# S1-C1-UPS.net
KiCad netlist of a schematic drawn in Altium Designer
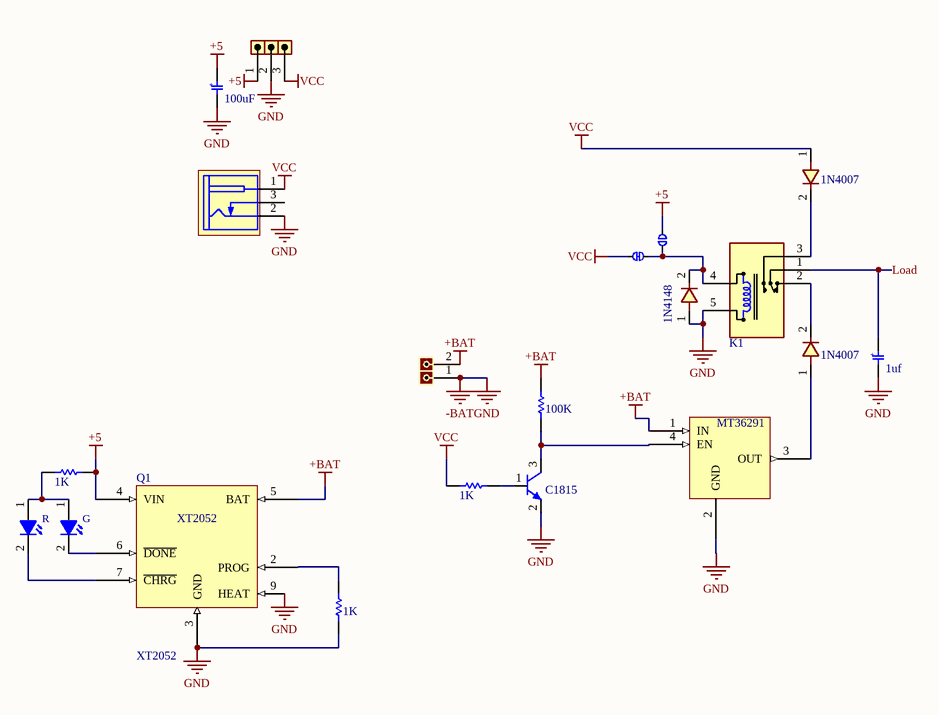
[diagram p0: S1-C1-UPS.SchDoc]

(export (version "E")
  (design (tool "Eeschema 10.0.6"))
  (components
    (comp (ref "*1") (value "SB-NC") (footprint "SB-NC") (libsource (lib "CustomLIB") (part "SB-NC")))
    (comp (ref "*2")
      (value "MT36291 Module")
      (footprint "Module")
      (libsource (lib "CustomLIB") (part "MT36291 Module"))
    )
    (comp (ref "C1")
      (value "100uF")
      (footprint "C_EL_8X12")
      (description "Capacitor Electrical THD")
      (libsource (lib "Capacitor") (part "Capacitor Electrical THD"))
    )
    (comp (ref "C2")
      (value "1uf")
      (footprint "C_EL_10X12")
      (description "Capacitor Electrical THD")
      (libsource (lib "Capacitor") (part "Capacitor Electrical THD"))
    )
    (comp (ref "D1")
      (value "1N4007")
      (footprint "D_SMA")
      (description "DIODE, GENERAL PURPOSE, 1000V/1A")
      (fields (field (name "Comment") "1N4007 SMD M7"))
      (libsource (lib "Diode") (part "1N4007 SMD M7"))
    )
    (comp (ref "D2")
      (value "1N4148")
      (footprint "D_SMA")
      (description "DIODE, GENERAL PURPOSE, 1000V/1A")
      (fields (field (name "Comment") "1N4007 SMD M7"))
      (libsource (lib "Diode") (part "1N4007 SMD M7"))
    )
    (comp (ref "D3")
      (value "1N4007")
      (footprint "D_SMA")
      (description "DIODE, GENERAL PURPOSE, 1000V/1A")
      (fields (field (name "Comment") "1N4007 SMD M7"))
      (libsource (lib "Diode") (part "1N4007 SMD M7"))
    )
    (comp (ref "D4")
      (value "R")
      (footprint "LED SMD 0805 (Red)")
      (description "LED SMD 0805")
      (libsource (lib "LED") (part "LED SMD 0805"))
    )
    (comp (ref "D5")
      (value "G")
      (footprint "LED SMD 0805 (Green)")
      (description "LED SMD 0805")
      (libsource (lib "LED") (part "LED SMD 0805"))
    )
    (comp (ref "J1")
      (value "Female Header Single 3")
      (footprint "HDR_F_1X3")
      (description "Female, pitch: 2.54mm")
      (libsource (lib "Header") (part "Female Header Single 3"))
    )
    (comp (ref "J2")
      (value "Power Jack")
      (footprint "POWER J1")
      (libsource (lib "Socket") (part "Power Jack"))
    )
    (comp (ref "K1")
      (value "RELAY SPST 5 Pin Millon")
      (footprint "REL_SPDT_5_2216")
      (description "Relay")
      (libsource (lib "Relay") (part "RELAY SPST 5 Pin Millon"))
    )
    (comp (ref "P1")
      (value "Male Header Single 02")
      (footprint "MHDR1X02-254P")
      (description "Male, pitch: 2.54mm")
      (libsource (lib "Header") (part "Male Header Single 02"))
    )
    (comp (ref "Q1") (value "XT2052") (footprint "XT2052") (libsource (lib "XT2052") (part "XT2052")))
    (comp (ref "Q2")
      (value "C1815")
      (footprint "SOT-23")
      (fields (field (name "Comment") "C1815 NPN"))
      (libsource (lib "Transistor") (part "C1815 NPN"))
    )
    (comp (ref "R1")
      (value "100K")
      (footprint "R0805")
      (description "Resistor SMD 0805")
      (libsource (lib "Resistor") (part "Resistor SMD 0805"))
    )
    (comp (ref "R2")
      (value "1K")
      (footprint "R0805")
      (description "Resistor SMD 0805")
      (libsource (lib "Resistor") (part "Resistor SMD 0805"))
    )
    (comp (ref "R3")
      (value "1K")
      (footprint "R0805")
      (description "Resistor SMD 0805")
      (libsource (lib "Resistor") (part "Resistor SMD 0805"))
    )
    (comp (ref "R4")
      (value "1K")
      (footprint "R0805")
      (description "Resistor SMD 0805")
      (libsource (lib "Resistor") (part "Resistor SMD 0805"))
    )
    (comp (ref "SB1") (value "Solid Bridge") (footprint "SB-NO") (libsource (lib "CustomLIB") (part "SB-NO")))
  )
  (nets
    (net (code "1") (name "+5") (class "Default")
      (node (ref "C1") (pin "1") (pinfunction "1_1") (pintype "passive"))
      (node (ref "J1") (pin "1") (pinfunction "1_1") (pintype "passive"))
      (node (ref "Q1") (pin "4") (pinfunction "VIN_4") (pintype "input"))
      (node (ref "R2") (pin "2") (pinfunction "2_2") (pintype "passive"))
      (node (ref "SB1") (pin "2") (pinfunction "2_2") (pintype "passive"))
    )
    (net (code "2") (name "+BAT") (class "Default")
      (node (ref "*2") (pin "1") (pinfunction "IN_1") (pintype "input"))
      (node (ref "P1") (pin "2") (pinfunction "2_2") (pintype "passive"))
      (node (ref "Q1") (pin "5") (pinfunction "BAT_5") (pintype "input"))
      (node (ref "R1") (pin "1") (pinfunction "1_1") (pintype "passive"))
    )
    (net (code "3") (name "-BAT") (class "Default")
      (node (ref "*2") (pin "2") (pinfunction "GND_2") (pintype "power_in"))
      (node (ref "C1") (pin "2") (pinfunction "2_2") (pintype "passive"))
      (node (ref "C2") (pin "2") (pinfunction "2_2") (pintype "passive"))
      (node (ref "D2") (pin "1") (pinfunction "1_1") (pintype "passive"))
      (node (ref "J1") (pin "2") (pinfunction "2_2") (pintype "passive"))
      (node (ref "J2") (pin "2") (pinfunction "SLEEVE_2") (pintype "power_in"))
      (node (ref "K1") (pin "5") (pinfunction "T2_5") (pintype "passive"))
      (node (ref "P1") (pin "1") (pinfunction "1_1") (pintype "passive"))
      (node (ref "Q1") (pin "3") (pinfunction "GND_3") (pintype "input"))
      (node (ref "Q1") (pin "9") (pinfunction "HEAT_9") (pintype "input"))
      (node (ref "Q2") (pin "2") (pinfunction "E_2") (pintype "passive"))
      (node (ref "R4") (pin "1") (pinfunction "1_1") (pintype "passive"))
    )
    (net (code "4") (name "/Load") (class "Default")
      (node (ref "C2") (pin "1") (pinfunction "1_1") (pintype "passive"))
      (node (ref "K1") (pin "1") (pinfunction "COM_1") (pintype "passive"))
    )
    (net (code "5") (name "Net-(*2-EN)") (class "Default")
      (node (ref "*2") (pin "4") (pinfunction "EN_4") (pintype "input"))
      (node (ref "Q2") (pin "3") (pinfunction "C_3") (pintype "passive"))
      (node (ref "R1") (pin "2") (pinfunction "2_2") (pintype "passive"))
    )
    (net (code "6") (name "Net-(*2-OUT)") (class "Default")
      (node (ref "*2") (pin "3") (pinfunction "OUT_3") (pintype "output"))
      (node (ref "D3") (pin "1") (pinfunction "1_1") (pintype "passive"))
    )
    (net (code "7") (name "Net-(D4-ANODE)") (class "Default")
      (node (ref "D4") (pin "1") (pinfunction "ANODE_1") (pintype "passive"))
      (node (ref "D5") (pin "1") (pinfunction "ANODE_1") (pintype "passive"))
      (node (ref "R2") (pin "1") (pinfunction "1_1") (pintype "passive"))
    )
    (net (code "8") (name "Net-(D4-CATHODE)") (class "Default")
      (node (ref "D4") (pin "2") (pinfunction "CATHODE_2") (pintype "passive"))
      (node (ref "Q1") (pin "7") (pinfunction "~{CHRG}_7") (pintype "input"))
    )
    (net (code "9") (name "Net-(D5-CATHODE)") (class "Default")
      (node (ref "D5") (pin "2") (pinfunction "CATHODE_2") (pintype "passive"))
      (node (ref "Q1") (pin "6") (pinfunction "~{DONE}_6") (pintype "input"))
    )
    (net (code "10") (name "Net-(K1-NC)") (class "Default")
      (node (ref "D3") (pin "2") (pinfunction "2_2") (pintype "passive"))
      (node (ref "K1") (pin "2") (pinfunction "NC_2") (pintype "passive"))
    )
    (net (code "11") (name "Net-(K1-NO)") (class "Default")
      (node (ref "D1") (pin "2") (pinfunction "2_2") (pintype "passive"))
      (node (ref "K1") (pin "3") (pinfunction "NO_3") (pintype "passive"))
    )
    (net (code "12") (name "Net-(K1-T1)") (class "Default")
      (node (ref "*1") (pin "1") (pinfunction "1_1") (pintype "passive"))
      (node (ref "D2") (pin "2") (pinfunction "2_2") (pintype "passive"))
      (node (ref "K1") (pin "4") (pinfunction "T1_4") (pintype "passive"))
      (node (ref "SB1") (pin "1") (pinfunction "1_1") (pintype "passive"))
    )
    (net (code "13") (name "Net-(Q1-PROG)") (class "Default")
      (node (ref "Q1") (pin "2") (pinfunction "PROG_2") (pintype "input"))
      (node (ref "R4") (pin "2") (pinfunction "2_2") (pintype "passive"))
    )
    (net (code "14") (name "Net-(Q2-B)") (class "Default")
      (node (ref "Q2") (pin "1") (pinfunction "B_1") (pintype "passive"))
      (node (ref "R3") (pin "1") (pinfunction "1_1") (pintype "passive"))
    )
    (net (code "15") (name "VCC") (class "Default")
      (node (ref "*1") (pin "2") (pinfunction "2_2") (pintype "passive"))
      (node (ref "D1") (pin "1") (pinfunction "1_1") (pintype "passive"))
      (node (ref "J1") (pin "3") (pinfunction "3_3") (pintype "passive"))
      (node (ref "J2") (pin "1") (pinfunction "TIP_1") (pintype "power_in"))
      (node (ref "R3") (pin "2") (pinfunction "2_2") (pintype "passive"))
    )
    (net (code "16") (name "unconnected-(J2-INSERTION_DET-Pad3)") (class "Default")
      (node (ref "J2") (pin "3") (pinfunction "INSERTION_DET_3") (pintype "power_in"))
    )
  )
)
